# Monitor-Protection_48V.net
KiCad netlist of a schematic drawn in Altium Designer
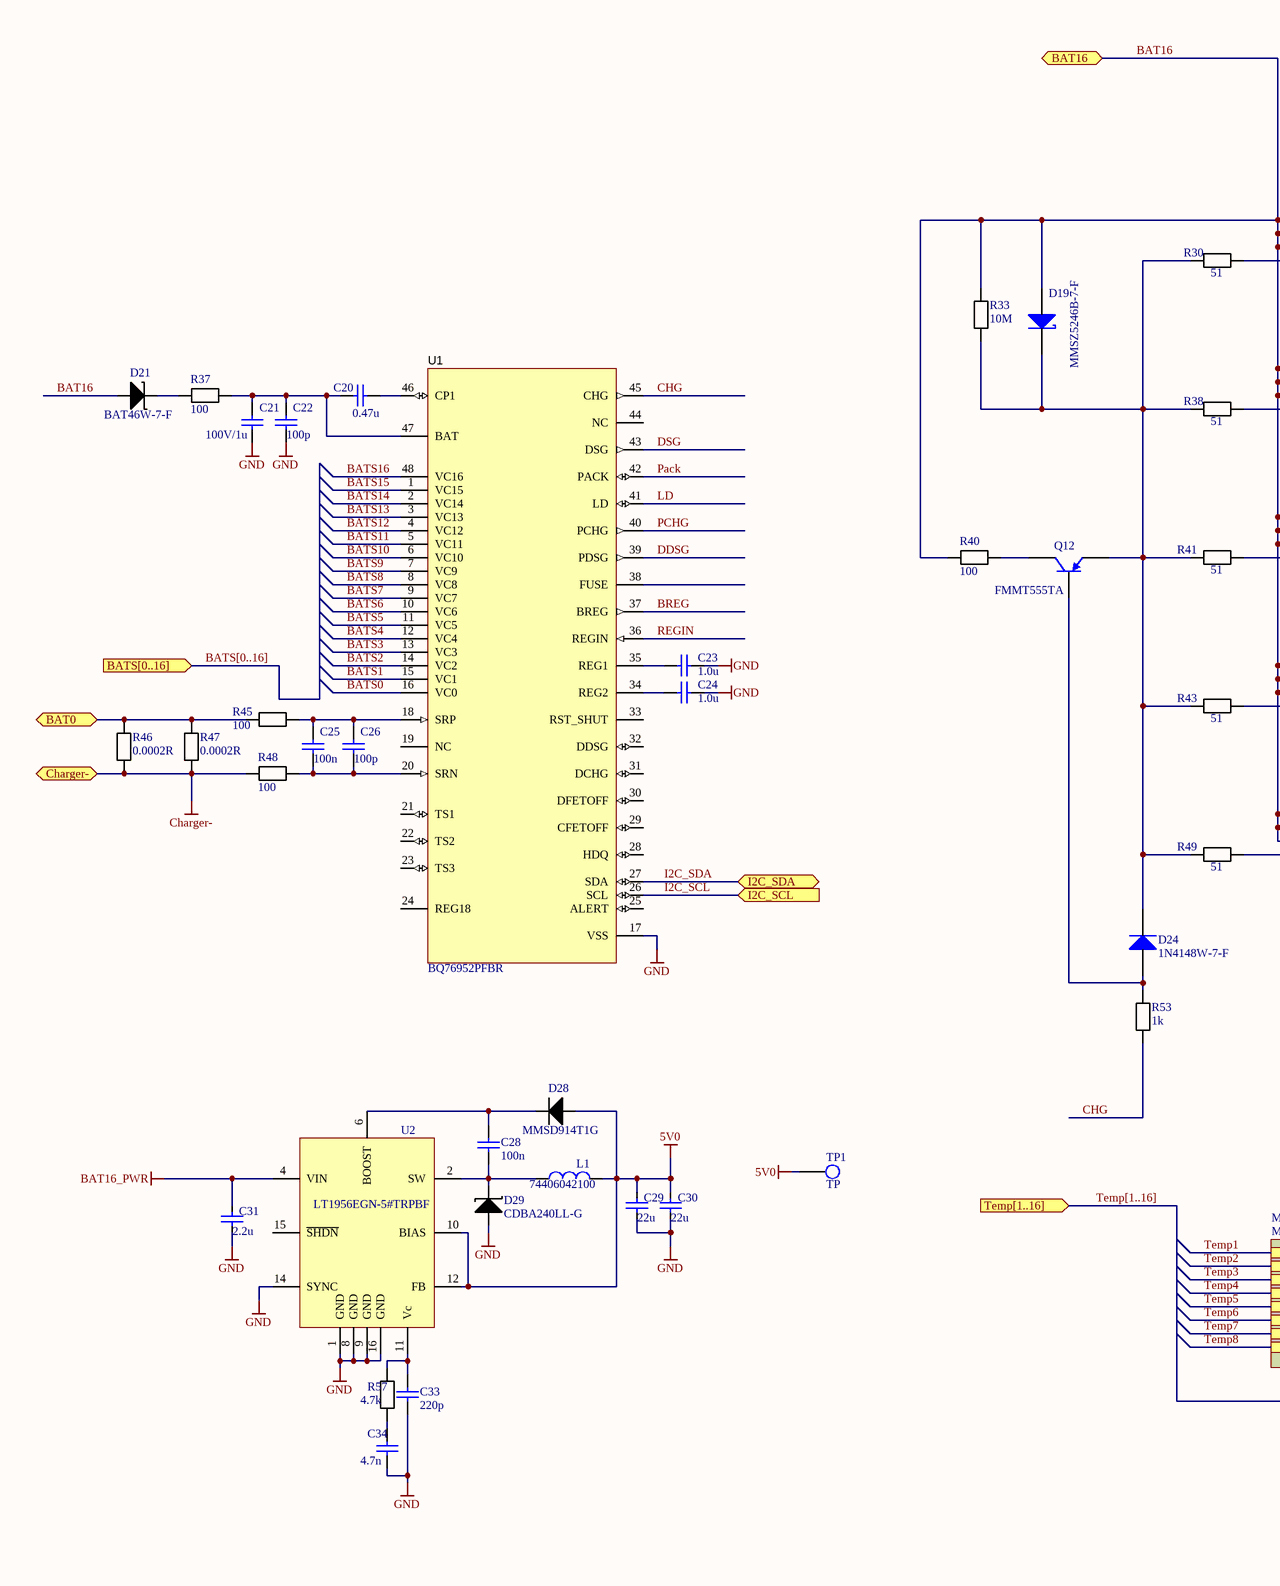
[diagram p0: Monitor-Protection_48V.SchDoc, left]
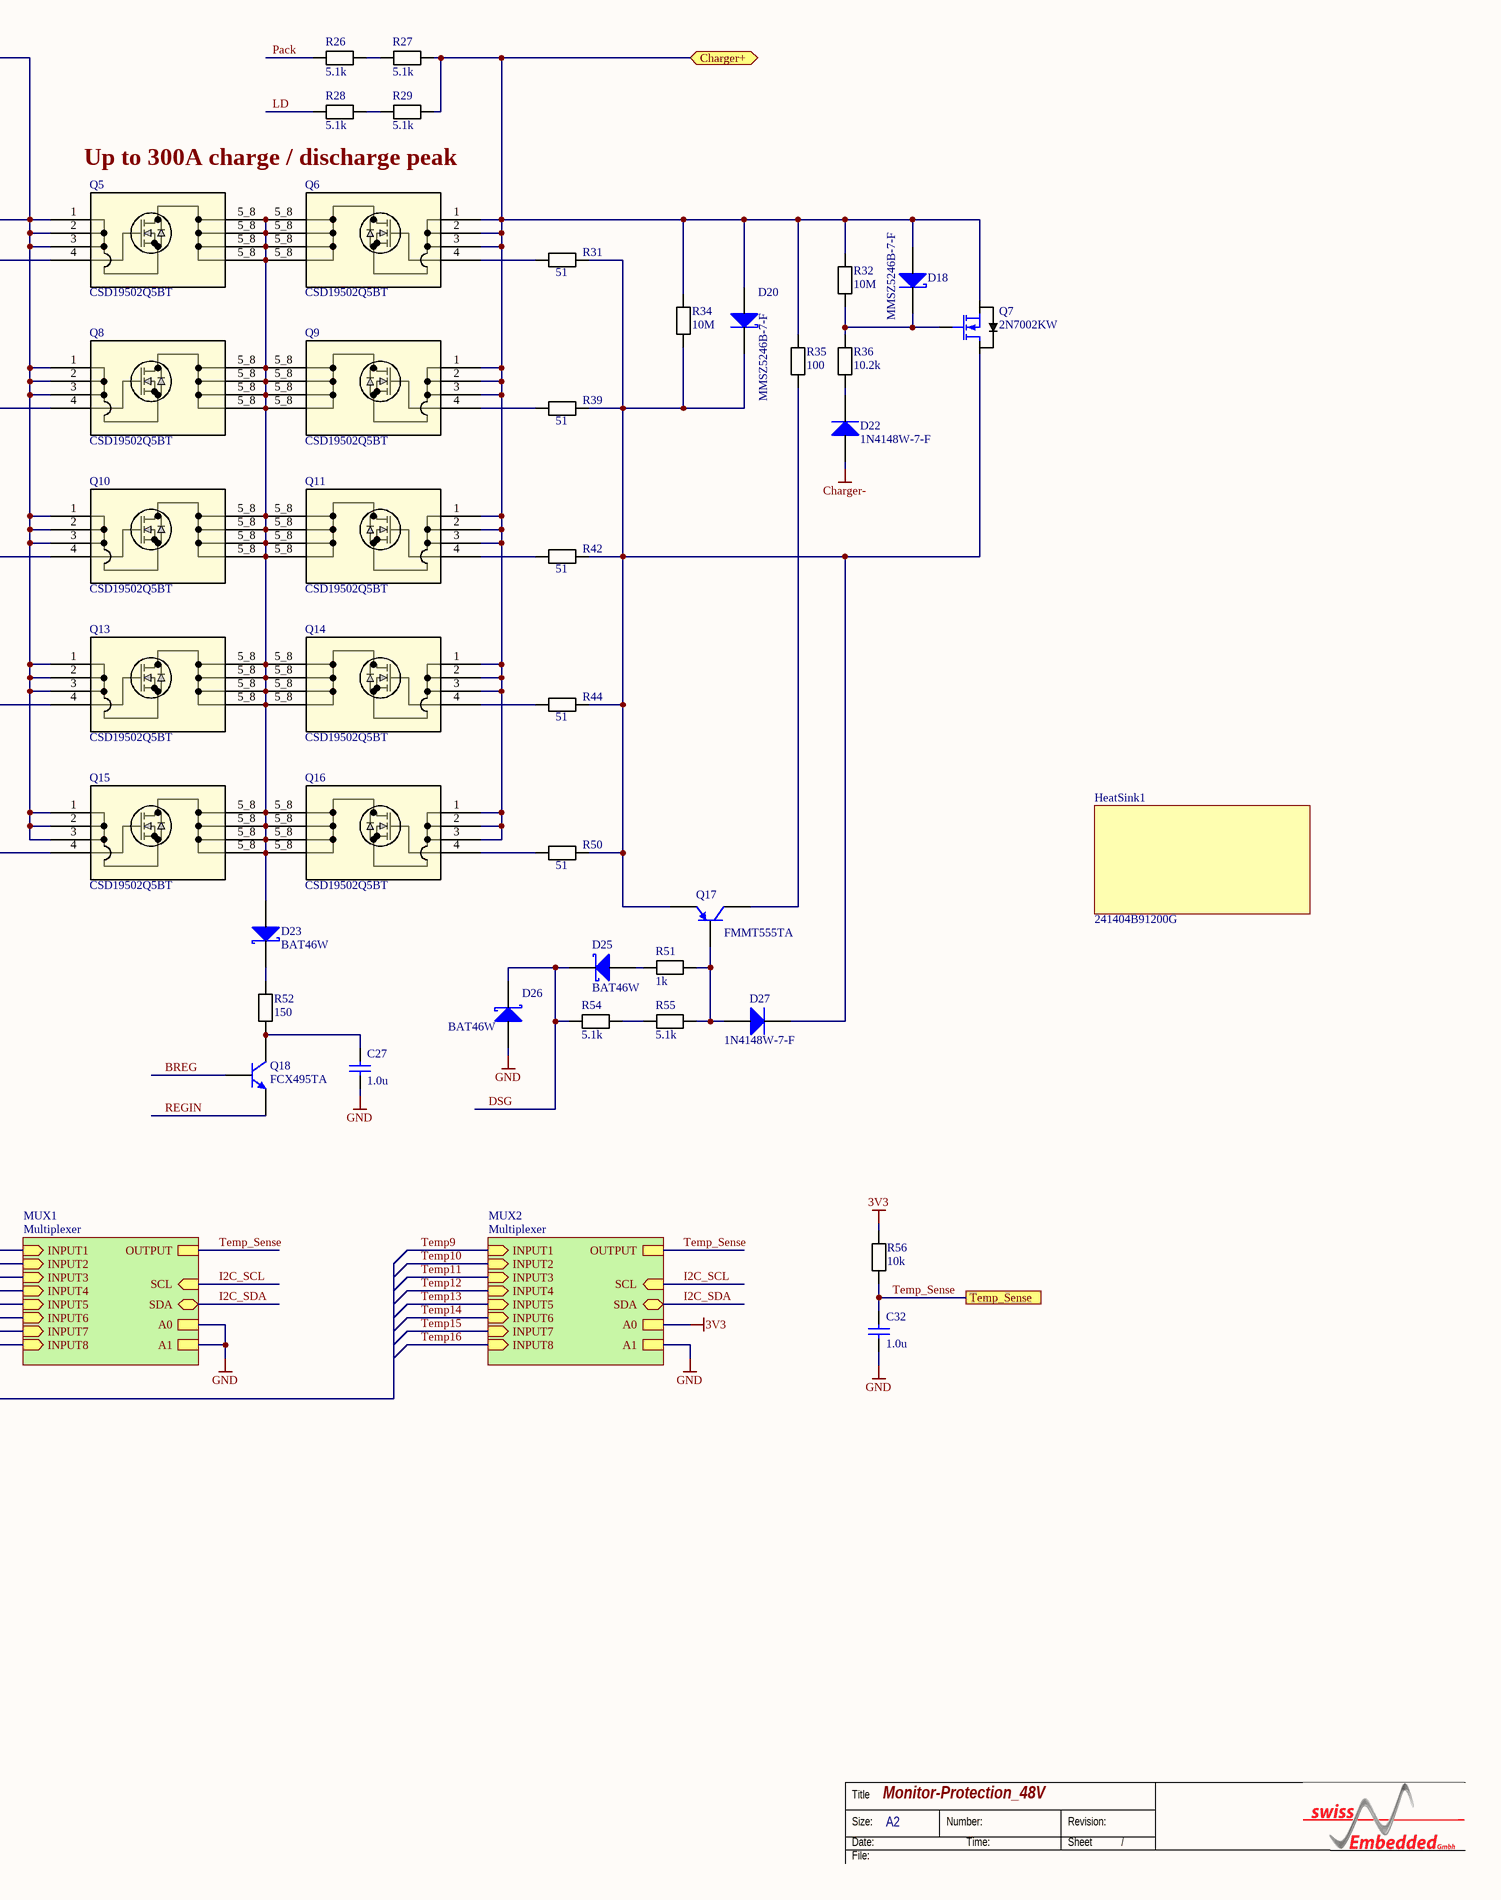
[diagram p1: Monitor-Protection_48V.SchDoc, right]

(export (version "E")
  (design (tool "Eeschema 10.0.6"))
  (components
    (comp (ref "C20")
      (value "0.47u")
      (footprint "C0805")
      (description "CAP CER 0.47UF 25V X7R 0805")
      (fields
        (field (name "MANUFACTURER") "Yageo")
        (field (name "MANUFACTURER PART NUMBER") "CC0805KKX7R8BB474")
      )
      (libsource (lib "RCL") (part "CAP"))
    )
    (comp (ref "C21")
      (value "100V/1u")
      (footprint "C1206")
      (description "Capacitor 1u 1206 +-10% 100V")
      (fields
        (field (name "MANUFACTURER") "Yageo")
        (field (name "MANUFACTURER PART NUMBER") "CC1206KKX7R0BB105")
      )
      (libsource (lib "EMDO301_Balancer_48V") (part "CC1206KKX7R0BB105"))
    )
    (comp (ref "C22")
      (value "100p")
      (footprint "C0603")
      (description "CAP CER 100PF 100V C0G/NP0 0603")
      (fields
        (field (name "MANUFACTURER") "Murata Electronics")
        (field (name "MANUFACTURER PART NUMBER") "GCM1885C2A101FA16D")
      )
      (libsource (lib "RCL") (part "CAP"))
    )
    (comp (ref "C23")
      (value "1.0u")
      (footprint "C0603")
      (description "CAP CER 1UF 25V X5R 0603")
      (fields
        (field (name "MANUFACTURER") "Yageo")
        (field (name "MANUFACTURER PART NUMBER") "CC0603KRX5R8BB105")
      )
      (libsource (lib "RCL") (part "CAP"))
    )
    (comp (ref "C24")
      (value "1.0u")
      (footprint "C0603")
      (description "CAP CER 1UF 25V X5R 0603")
      (fields
        (field (name "MANUFACTURER") "Yageo")
        (field (name "MANUFACTURER PART NUMBER") "CC0603KRX5R8BB105")
      )
      (libsource (lib "RCL") (part "CAP"))
    )
    (comp (ref "C25")
      (value "100n")
      (footprint "C0603")
      (description "Capacitor 100n 0603 +-10% 50V")
      (fields
        (field (name "PART NUMBER") "CAP_YAG_CC0603KRX7R9BB104_X7R")
        (field (name "MANUFACTURER PART NUMBER") "CC0603KRX7R9BB104")
      )
      (libsource (lib "EMDO301_Balancer_48V") (part "CAP_YAG_CC0603KRX7R9BB104_X7R"))
    )
    (comp (ref "C26")
      (value "100p")
      (footprint "C0603")
      (description "CAP CER 100PF 100V C0G/NP0 0603")
      (fields
        (field (name "MANUFACTURER") "Murata Electronics")
        (field (name "MANUFACTURER PART NUMBER") "GCM1885C2A101FA16D")
      )
      (libsource (lib "RCL") (part "CAP"))
    )
    (comp (ref "C27")
      (value "1.0u")
      (footprint "C0603")
      (description "CAP CER 1UF 25V X5R 0603")
      (fields
        (field (name "MANUFACTURER") "Yageo")
        (field (name "MANUFACTURER PART NUMBER") "CC0603KRX5R8BB105")
      )
      (libsource (lib "RCL") (part "CAP"))
    )
    (comp (ref "C28")
      (value "100n")
      (footprint "C0603")
      (description "Capacitor 100n 0603 +-10% 50V")
      (fields
        (field (name "PART NUMBER") "CAP_YAG_CC0603KRX7R9BB104_X7R")
        (field (name "MANUFACTURER PART NUMBER") "CC0603KRX7R9BB104")
      )
      (libsource (lib "EMDO301_Balancer_48V") (part "CAP_YAG_CC0603KRX7R9BB104_X7R"))
    )
    (comp (ref "C29")
      (value "22u")
      (footprint "C1210")
      (description "22µF ±10% 10V")
      (fields
        (field (name "MANUFACTURER") "Murata")
        (field (name "MANUFACTURER PART NUMBER") "GRM32ER71A226KE20L")
      )
      (libsource (lib "Miscellaneous Devices") (part "Cap"))
    )
    (comp (ref "C30")
      (value "22u")
      (footprint "C1210")
      (description "22µF ±10% 10V")
      (fields
        (field (name "MANUFACTURER") "Murata")
        (field (name "MANUFACTURER PART NUMBER") "GRM32ER71A226KE20L")
      )
      (libsource (lib "Miscellaneous Devices") (part "Cap"))
    )
    (comp (ref "C31")
      (value "2.2u")
      (footprint "C1210")
      (description "2.2µF ±10% 100V")
      (fields
        (field (name "MANUFACTURER") "Murata")
        (field (name "MANUFACTURER PART NUMBER") "GRM32ER72A225KA35K")
      )
      (libsource (lib "Miscellaneous Devices") (part "Cap"))
    )
    (comp (ref "C32")
      (value "1.0u")
      (footprint "C0603")
      (description "CAP CER 1UF 25V X5R 0603")
      (fields
        (field (name "MANUFACTURER") "Yageo")
        (field (name "MANUFACTURER PART NUMBER") "CC0603KRX5R8BB105")
      )
      (libsource (lib "RCL") (part "CAP"))
    )
    (comp (ref "C33")
      (value "220p")
      (footprint "C0603")
      (description "Capacitor 220p 0603 +-10% 50V")
      (fields
        (field (name "PART NUMBER") "CAP_YAG_CC0603KRNPO9BN221_NPO")
        (field (name "MANUFACTURER") "Yageo")
      )
      (libsource (lib "Cap_Yag_0603_NPO_50_10%$") (part "CAP_YAG_CC0603KRNPO9BN221_NPO"))
    )
    (comp (ref "C34")
      (value "4.7n")
      (footprint "C0603")
      (description "Capacitor 4.7n 0603 +-10% 50V")
      (fields
        (field (name "PART NUMBER") "CAP_YAG_CC0603KRX7R9BB472_X7R")
        (field (name "MANUFACTURER") "Yageo")
      )
      (libsource (lib "Cap_Yag_0603_X7R_50_10%$") (part "CAP_YAG_CC0603KRX7R9BB472_X7R"))
    )
    (comp (ref "D18")
      (value "MMSZ5246B-7-F")
      (footprint "SOD-323")
      (description "Diode, Zener, 16 V, 500 mW, SOD-323")
      (fields (field (name "MANUFACTURER") "Diodes") (field (name "TOLERANCE") "+-5%"))
      (libsource (lib "Battery") (part "VD_SMD_MMSZ5246B-7-F"))
    )
    (comp (ref "D19")
      (value "MMSZ5246B-7-F")
      (footprint "SOD-323")
      (description "Diode, Zener, 16 V, 500 mW, SOD-323")
      (fields (field (name "MANUFACTURER") "Diodes") (field (name "TOLERANCE") "+-5%"))
      (libsource (lib "Battery") (part "VD_SMD_MMSZ5246B-7-F"))
    )
    (comp (ref "D20")
      (value "MMSZ5246B-7-F")
      (footprint "SOD-323")
      (description "Diode, Zener, 16 V, 500 mW, SOD-323")
      (fields (field (name "MANUFACTURER") "Diodes") (field (name "TOLERANCE") "+-5%"))
      (libsource (lib "Battery") (part "VD_SMD_MMSZ5246B-7-F"))
    )
    (comp (ref "D21")
      (value "BAT46W-7-F")
      (footprint "SOD123")
      (description "DIODE SCHOTTKY 100V 150MA SOD123")
      (fields (field (name "MANUFACTURER") "Diodes Incorporated"))
      (libsource (lib "EnergyMeter") (part "BAT46W-7-F"))
    )
    (comp (ref "D22")
      (value "1N4148W-7-F")
      (footprint "SOD123")
      (description "Diode, Ultrafast, 100 V, 0.15 A, SOD-123")
      (fields (field (name "MANUFACTURER") "Diodes Inc.") (field (name "MANUFACTURER PART NUMBER") "1N4148"))
      (libsource (lib "Battery") (part "VD_SMD_1N4148"))
    )
    (comp (ref "D23")
      (value "BAT46W")
      (footprint "SOD123")
      (description "Diode, Schottky, 100 V, 0.15 A, SOD-123")
      (fields
        (field (name "MANUFACTURER") "CENTRAL SEMI")
        (field (name "MANUFACTURER PART NUMBER") "CMMSH2-40 TR")
      )
      (libsource (lib "Battery") (part "VD_SMD_BAT46W"))
    )
    (comp (ref "D24")
      (value "1N4148W-7-F")
      (footprint "SOD123")
      (description "Diode, Ultrafast, 100 V, 0.15 A, SOD-123")
      (fields (field (name "MANUFACTURER") "Diodes Inc.") (field (name "MANUFACTURER PART NUMBER") "1N4148"))
      (libsource (lib "Battery") (part "VD_SMD_1N4148"))
    )
    (comp (ref "D25")
      (value "BAT46W")
      (footprint "SOD123")
      (description "Diode, Schottky, 100 V, 0.15 A, SOD-123")
      (fields
        (field (name "MANUFACTURER") "CENTRAL SEMI")
        (field (name "MANUFACTURER PART NUMBER") "CMMSH2-40 TR")
      )
      (libsource (lib "Battery") (part "VD_SMD_BAT46W"))
    )
    (comp (ref "D26")
      (value "BAT46W")
      (footprint "SOD123")
      (description "Diode, Schottky, 100 V, 0.15 A, SOD-123")
      (fields
        (field (name "MANUFACTURER") "CENTRAL SEMI")
        (field (name "MANUFACTURER PART NUMBER") "CMMSH2-40 TR")
      )
      (libsource (lib "Battery") (part "VD_SMD_BAT46W"))
    )
    (comp (ref "D27")
      (value "1N4148W-7-F")
      (footprint "SOD123")
      (description "Diode, Ultrafast, 100 V, 0.15 A, SOD-123")
      (fields (field (name "MANUFACTURER") "Diodes Inc.") (field (name "MANUFACTURER PART NUMBER") "1N4148"))
      (libsource (lib "Battery") (part "VD_SMD_1N4148"))
    )
    (comp (ref "D28")
      (value "MMSD914T1G")
      (footprint "SOD123")
      (description "DIODE GEN PURP 100V 200MA SOD123")
      (fields (field (name "MANUFACTURER") "ON Semiconductor"))
      (libsource (lib "EnergyMeter") (part "MMSD914T1G"))
    )
    (comp (ref "D29")
      (value "CDBA240LL-G")
      (footprint "DO-214AC")
      (description "DIODE SCHOTTKY 40V 2A DO214AC")
      (fields (field (name "MANUFACTURER") "Comchip Technology"))
      (libsource (lib "EnergyMeter") (part "CDBA240LL-G"))
    )
    (comp (ref "HeatSink1")
      (value "241404B91200G")
      (footprint "HeatSink_241404B91200G")
      (description "Heat Sinks Heat Sink for Quarter Brick DC/DC Converters, Lengthwise Fins, 11.4mm Height")
      (fields (field (name "MANUFACTURER") "Aavid"))
      (libsource (lib "EMDO301_Balancer_48V") (part "HeatSink"))
    )
    (comp (ref "L1")
      (value "74406042100")
      (footprint "WURTH_74406042100")
      (description "FIXED IND 10UH 1.61A 133MOHM SMD")
      (fields (field (name "MANUFACTURER") "Würth Elektronik"))
      (libsource (lib "WirelessCharger") (part "Inductor"))
    )
    (comp (ref "Q5")
      (value "CSD19502Q5BT")
      (footprint "TRANS_CSD19502Q5BT")
      (description "MOSFET N-Channel, 3.4mOhm 80V")
      (fields (field (name "MANUFACTURER") "TI") (field (name "TOLERANCE") "+-5%"))
      (libsource (lib "Battery") (part "VT_FET_CSD19532Q5B"))
    )
    (comp (ref "Q6")
      (value "CSD19502Q5BT")
      (footprint "TRANS_CSD19502Q5BT")
      (description "MOSFET N-Channel, 3.4mOhm 80V")
      (fields (field (name "MANUFACTURER") "TI") (field (name "TOLERANCE") "+-5%"))
      (libsource (lib "Battery") (part "VT_FET_CSD19532Q5B"))
    )
    (comp (ref "Q7")
      (value "2N7002KW")
      (footprint "SOT-323")
      (description "MOSFET, N-CH, 60 V, 0.31 A, SOT-323")
      (fields (field (name "MANUFACTURER") "Fairchild"))
      (libsource (lib "Battery") (part "VT_FET_2N7002KW"))
    )
    (comp (ref "Q8")
      (value "CSD19502Q5BT")
      (footprint "TRANS_CSD19502Q5BT")
      (description "MOSFET N-Channel, 3.4mOhm 80V")
      (fields (field (name "MANUFACTURER") "TI") (field (name "TOLERANCE") "+-5%"))
      (libsource (lib "Battery") (part "VT_FET_CSD19532Q5B"))
    )
    (comp (ref "Q9")
      (value "CSD19502Q5BT")
      (footprint "TRANS_CSD19502Q5BT")
      (description "MOSFET N-Channel, 3.4mOhm 80V")
      (fields (field (name "MANUFACTURER") "TI") (field (name "TOLERANCE") "+-5%"))
      (libsource (lib "Battery") (part "VT_FET_CSD19532Q5B"))
    )
    (comp (ref "Q10")
      (value "CSD19502Q5BT")
      (footprint "TRANS_CSD19502Q5BT")
      (description "MOSFET N-Channel, 3.4mOhm 80V")
      (fields (field (name "MANUFACTURER") "TI") (field (name "TOLERANCE") "+-5%"))
      (libsource (lib "Battery") (part "VT_FET_CSD19532Q5B"))
    )
    (comp (ref "Q11")
      (value "CSD19502Q5BT")
      (footprint "TRANS_CSD19502Q5BT")
      (description "MOSFET N-Channel, 3.4mOhm 80V")
      (fields (field (name "MANUFACTURER") "TI") (field (name "TOLERANCE") "+-5%"))
      (libsource (lib "Battery") (part "VT_FET_CSD19532Q5B"))
    )
    (comp (ref "Q12")
      (value "FMMT555TA")
      (footprint "SOT23-3N")
      (description "TRANS PNP 150V 1A SOT23-3")
      (fields (field (name "MANUFACTURER") "Diodes"))
      (libsource (lib "EnergyMeter") (part "FMMT555TA"))
    )
    (comp (ref "Q13")
      (value "CSD19502Q5BT")
      (footprint "TRANS_CSD19502Q5BT")
      (description "MOSFET N-Channel, 3.4mOhm 80V")
      (fields (field (name "MANUFACTURER") "TI") (field (name "TOLERANCE") "+-5%"))
      (libsource (lib "Battery") (part "VT_FET_CSD19532Q5B"))
    )
    (comp (ref "Q14")
      (value "CSD19502Q5BT")
      (footprint "TRANS_CSD19502Q5BT")
      (description "MOSFET N-Channel, 3.4mOhm 80V")
      (fields (field (name "MANUFACTURER") "TI") (field (name "TOLERANCE") "+-5%"))
      (libsource (lib "Battery") (part "VT_FET_CSD19532Q5B"))
    )
    (comp (ref "Q15")
      (value "CSD19502Q5BT")
      (footprint "TRANS_CSD19502Q5BT")
      (description "MOSFET N-Channel, 3.4mOhm 80V")
      (fields (field (name "MANUFACTURER") "TI") (field (name "TOLERANCE") "+-5%"))
      (libsource (lib "Battery") (part "VT_FET_CSD19532Q5B"))
    )
    (comp (ref "Q16")
      (value "CSD19502Q5BT")
      (footprint "TRANS_CSD19502Q5BT")
      (description "MOSFET N-Channel, 3.4mOhm 80V")
      (fields (field (name "MANUFACTURER") "TI") (field (name "TOLERANCE") "+-5%"))
      (libsource (lib "Battery") (part "VT_FET_CSD19532Q5B"))
    )
    (comp (ref "Q17")
      (value "FMMT555TA")
      (footprint "SOT23-3N")
      (description "TRANS PNP 150V 1A SOT23-3")
      (fields (field (name "MANUFACTURER") "Diodes"))
      (libsource (lib "EnergyMeter") (part "FMMT555TA"))
    )
    (comp (ref "Q18")
      (value "FCX495TA")
      (footprint "SOT-89")
      (description "Transistor, NPN, 150 V, 1 A, AEC-Q101, SOT-89")
      (fields (field (name "MANUFACTURER") "Diodes"))
      (libsource (lib "Battery") (part "FCX495TA"))
    )
    (comp (ref "R26")
      (value "5.1k")
      (footprint "R0603")
      (description "Resistor 5.1k 0603 +-1% 0.1")
      (fields (field (name "PART NUMBER") "RES_YAG_RC0603FR-075K1L") (field (name "MANUFACTURER") "Yageo"))
      (libsource (lib "Res_Yag_0603_1%$") (part "RES_YAG_RC0603FR-075K1L"))
    )
    (comp (ref "R27")
      (value "5.1k")
      (footprint "R0603")
      (description "Resistor 5.1k 0603 +-1% 0.1")
      (fields (field (name "PART NUMBER") "RES_YAG_RC0603FR-075K1L") (field (name "MANUFACTURER") "Yageo"))
      (libsource (lib "Res_Yag_0603_1%$") (part "RES_YAG_RC0603FR-075K1L"))
    )
    (comp (ref "R28")
      (value "5.1k")
      (footprint "R0603")
      (description "Resistor 5.1k 0603 +-1% 0.1")
      (fields (field (name "PART NUMBER") "RES_YAG_RC0603FR-075K1L") (field (name "MANUFACTURER") "Yageo"))
      (libsource (lib "Res_Yag_0603_1%$") (part "RES_YAG_RC0603FR-075K1L"))
    )
    (comp (ref "R29")
      (value "5.1k")
      (footprint "R0603")
      (description "Resistor 5.1k 0603 +-1% 0.1")
      (fields (field (name "PART NUMBER") "RES_YAG_RC0603FR-075K1L") (field (name "MANUFACTURER") "Yageo"))
      (libsource (lib "Res_Yag_0603_1%$") (part "RES_YAG_RC0603FR-075K1L"))
    )
    (comp (ref "R30")
      (value "51")
      (footprint "R0603")
      (description "Resistor 51 0603 +-1% 0.1")
      (fields (field (name "PART NUMBER") "RES_YAG_RC0603FR-0751RL") (field (name "MANUFACTURER") "Yageo"))
      (libsource (lib "Res_Yag_0603_1%$") (part "RES_YAG_RC0603FR-0751RL"))
    )
    (comp (ref "R31")
      (value "51")
      (footprint "R0603")
      (description "Resistor 51 0603 +-1% 0.1")
      (fields (field (name "PART NUMBER") "RES_YAG_RC0603FR-0751RL") (field (name "MANUFACTURER") "Yageo"))
      (libsource (lib "Res_Yag_0603_1%$") (part "RES_YAG_RC0603FR-0751RL"))
    )
    (comp (ref "R32")
      (value "10M")
      (footprint "R0603")
      (description "Resistor 10M 0603 +-1% 0.1")
      (fields (field (name "PART NUMBER") "RES_YAG_RC0603FR-0710ML") (field (name "MANUFACTURER") "Yageo"))
      (libsource (lib "Res_Yag_0603_1%$") (part "RES_YAG_RC0603FR-0710ML"))
    )
    (comp (ref "R33")
      (value "10M")
      (footprint "R0603")
      (description "Resistor 10M 0603 +-1% 0.1")
      (fields (field (name "PART NUMBER") "RES_YAG_RC0603FR-0710ML") (field (name "MANUFACTURER") "Yageo"))
      (libsource (lib "Res_Yag_0603_1%$") (part "RES_YAG_RC0603FR-0710ML"))
    )
    (comp (ref "R34")
      (value "10M")
      (footprint "R0603")
      (description "Resistor 10M 0603 +-1% 0.1")
      (fields (field (name "PART NUMBER") "RES_YAG_RC0603FR-0710ML") (field (name "MANUFACTURER") "Yageo"))
      (libsource (lib "Res_Yag_0603_1%$") (part "RES_YAG_RC0603FR-0710ML"))
    )
    (comp (ref "R35")
      (value "100")
      (footprint "R0603")
      (description "Resistor 100 0603 +-1% 0.1")
      (fields (field (name "PART NUMBER") "RES_YAG_RC0603FR-07100RL") (field (name "MANUFACTURER") "Yageo"))
      (libsource (lib "Res_Yag_0603_1%$") (part "RES_YAG_RC0603FR-07100RL"))
    )
    (comp (ref "R36")
      (value "10.2k")
      (footprint "R0603")
      (description "Resistor 10.2k 0603 +-1% 0.1")
      (fields (field (name "PART NUMBER") "RES_YAG_RC0603FR-0710K2L") (field (name "MANUFACTURER") "Yageo"))
      (libsource (lib "Res_Yag_0603_1%$") (part "RES_YAG_RC0603FR-0710K2L"))
    )
    (comp (ref "R37")
      (value "100")
      (footprint "R0603")
      (description "Resistor 100 0603 +-1% 0.1")
      (fields (field (name "PART NUMBER") "RES_YAG_RC0603FR-07100RL") (field (name "MANUFACTURER") "Yageo"))
      (libsource (lib "Res_Yag_0603_1%$") (part "RES_YAG_RC0603FR-07100RL"))
    )
    (comp (ref "R38")
      (value "51")
      (footprint "R0603")
      (description "Resistor 51 0603 +-1% 0.1")
      (fields (field (name "PART NUMBER") "RES_YAG_RC0603FR-0751RL") (field (name "MANUFACTURER") "Yageo"))
      (libsource (lib "Res_Yag_0603_1%$") (part "RES_YAG_RC0603FR-0751RL"))
    )
    (comp (ref "R39")
      (value "51")
      (footprint "R0603")
      (description "Resistor 51 0603 +-1% 0.1")
      (fields (field (name "PART NUMBER") "RES_YAG_RC0603FR-0751RL") (field (name "MANUFACTURER") "Yageo"))
      (libsource (lib "Res_Yag_0603_1%$") (part "RES_YAG_RC0603FR-0751RL"))
    )
    (comp (ref "R40")
      (value "100")
      (footprint "R0603")
      (description "Resistor 100 0603 +-1% 0.1")
      (fields (field (name "PART NUMBER") "RES_YAG_RC0603FR-07100RL") (field (name "MANUFACTURER") "Yageo"))
      (libsource (lib "Res_Yag_0603_1%$") (part "RES_YAG_RC0603FR-07100RL"))
    )
    (comp (ref "R41")
      (value "51")
      (footprint "R0603")
      (description "Resistor 51 0603 +-1% 0.1")
      (fields (field (name "PART NUMBER") "RES_YAG_RC0603FR-0751RL") (field (name "MANUFACTURER") "Yageo"))
      (libsource (lib "Res_Yag_0603_1%$") (part "RES_YAG_RC0603FR-0751RL"))
    )
    (comp (ref "R42")
      (value "51")
      (footprint "R0603")
      (description "Resistor 51 0603 +-1% 0.1")
      (fields (field (name "PART NUMBER") "RES_YAG_RC0603FR-0751RL") (field (name "MANUFACTURER") "Yageo"))
      (libsource (lib "Res_Yag_0603_1%$") (part "RES_YAG_RC0603FR-0751RL"))
    )
    (comp (ref "R43")
      (value "51")
      (footprint "R0603")
      (description "Resistor 51 0603 +-1% 0.1")
      (fields (field (name "PART NUMBER") "RES_YAG_RC0603FR-0751RL") (field (name "MANUFACTURER") "Yageo"))
      (libsource (lib "Res_Yag_0603_1%$") (part "RES_YAG_RC0603FR-0751RL"))
    )
    (comp (ref "R44")
      (value "51")
      (footprint "R0603")
      (description "Resistor 51 0603 +-1% 0.1")
      (fields (field (name "PART NUMBER") "RES_YAG_RC0603FR-0751RL") (field (name "MANUFACTURER") "Yageo"))
      (libsource (lib "Res_Yag_0603_1%$") (part "RES_YAG_RC0603FR-0751RL"))
    )
    (comp (ref "R45")
      (value "100")
      (footprint "R0603")
      (description "Resistor 100 0603 +-1% 0.1")
      (fields (field (name "PART NUMBER") "RES_YAG_RC0603FR-07100RL") (field (name "MANUFACTURER") "Yageo"))
      (libsource (lib "Res_Yag_0603_1%$") (part "RES_YAG_RC0603FR-07100RL"))
    )
    (comp (ref "R46")
      (value "0.0002R")
      (footprint "RES 3920")
      (description "RES 0.0002 OHM 1% 12W 3920")
      (fields
        (field (name "MANUFACTURER") "Bourns Inc.")
        (field (name "MANUFACTURER PART NUMBER") "CSS2H-3920R-L200FE")
      )
      (libsource (lib "RCL") (part "RES"))
    )
    (comp (ref "R47")
      (value "0.0002R")
      (footprint "RES 3920")
      (description "RES 0.0002 OHM 1% 12W 3920")
      (fields
        (field (name "MANUFACTURER") "Bourns Inc.")
        (field (name "MANUFACTURER PART NUMBER") "CSS2H-3920R-L200FE")
      )
      (libsource (lib "RCL") (part "RES"))
    )
    (comp (ref "R48")
      (value "100")
      (footprint "R0603")
      (description "Resistor 100 0603 +-1% 0.1")
      (fields (field (name "PART NUMBER") "RES_YAG_RC0603FR-07100RL") (field (name "MANUFACTURER") "Yageo"))
      (libsource (lib "Res_Yag_0603_1%$") (part "RES_YAG_RC0603FR-07100RL"))
    )
    (comp (ref "R49")
      (value "51")
      (footprint "R0603")
      (description "Resistor 51 0603 +-1% 0.1")
      (fields (field (name "PART NUMBER") "RES_YAG_RC0603FR-0751RL") (field (name "MANUFACTURER") "Yageo"))
      (libsource (lib "Res_Yag_0603_1%$") (part "RES_YAG_RC0603FR-0751RL"))
    )
    (comp (ref "R50")
      (value "51")
      (footprint "R0603")
      (description "Resistor 51 0603 +-1% 0.1")
      (fields (field (name "PART NUMBER") "RES_YAG_RC0603FR-0751RL") (field (name "MANUFACTURER") "Yageo"))
      (libsource (lib "Res_Yag_0603_1%$") (part "RES_YAG_RC0603FR-0751RL"))
    )
    (comp (ref "R51")
      (value "1k")
      (footprint "R0603")
      (description "Resistor 1k 0603 +-1% 0.1")
      (fields (field (name "PART NUMBER") "RES_YAG_RC0603FR-071KL") (field (name "MANUFACTURER") "Yageo"))
      (libsource (lib "Res_Yag_0603_1%$") (part "RES_YAG_RC0603FR-071KL"))
    )
    (comp (ref "R52")
      (value "150")
      (footprint "R0603")
      (description "Resistor 150 0603 +-1% 0.1")
      (fields (field (name "PART NUMBER") "RES_YAG_RC0603FR-07150RL") (field (name "MANUFACTURER") "Yageo"))
      (libsource (lib "Res_Yag_0603_1%$") (part "RES_YAG_RC0603FR-07150RL"))
    )
    (comp (ref "R53")
      (value "1k")
      (footprint "R0603")
      (description "Resistor 1k 0603 +-1% 0.1")
      (fields (field (name "PART NUMBER") "RES_YAG_RC0603FR-071KL") (field (name "MANUFACTURER") "Yageo"))
      (libsource (lib "Res_Yag_0603_1%$") (part "RES_YAG_RC0603FR-071KL"))
    )
    (comp (ref "R54")
      (value "5.1k")
      (footprint "R0603")
      (description "Resistor 5.1k 0603 +-1% 0.1")
      (fields (field (name "PART NUMBER") "RES_YAG_RC0603FR-075K1L") (field (name "MANUFACTURER") "Yageo"))
      (libsource (lib "Res_Yag_0603_1%$") (part "RES_YAG_RC0603FR-075K1L"))
    )
    (comp (ref "R55")
      (value "5.1k")
      (footprint "R0603")
      (description "Resistor 5.1k 0603 +-1% 0.1")
      (fields (field (name "PART NUMBER") "RES_YAG_RC0603FR-075K1L") (field (name "MANUFACTURER") "Yageo"))
      (libsource (lib "Res_Yag_0603_1%$") (part "RES_YAG_RC0603FR-075K1L"))
    )
    (comp (ref "R56")
      (value "10k")
      (footprint "R0603")
      (description "Resistor 10k 0603 +-1% 0.1")
      (fields (field (name "PART NUMBER") "RES_YAG_RC0603FR-0710KL") (field (name "MANUFACTURER") "Yageo"))
      (libsource (lib "Res_Yag_0603_1%$") (part "RES_YAG_RC0603FR-0710KL"))
    )
    (comp (ref "R57")
      (value "4.7k")
      (footprint "R0603")
      (description "Resistor 4.7k 0603 +-1% 0.1")
      (fields (field (name "PART NUMBER") "RES_YAG_RC0603FR-074K7L") (field (name "MANUFACTURER") "Yageo"))
      (libsource (lib "Res_Yag_0603_1%$") (part "RES_YAG_RC0603FR-074K7L"))
    )
    (comp (ref "TP1")
      (value "TP")
      (footprint "TP")
      (description "Testpoint")
      (fields
        (field (name "MANUFACTURER") "None")
        (field (name "MANUFACTURER PART NUMBER") "Testpads, do not populate")
      )
      (libsource (lib "EnergyMeter") (part "TP"))
    )
    (comp (ref "U1")
      (value "BQ76952PFBR")
      (footprint "QFP50P900X900X120-48N")
      (description "Multicell Battery Monitor and Protection Family, Texas Instrument BQ76952PFBR")
      (fields (field (name "MANUFACTURER") "Texas Instruments"))
      (libsource (lib "EMDO301_Balancer_48V") (part "BQ76952PFBR"))
    )
    (comp (ref "U2")
      (value "LT1956EGN-5#TRPBF")
      (footprint "SSOP-16_GN")
      (description "IC REG BUCK 5V 1.5A 16SSOP")
      (fields (field (name "MANUFACTURER") "Analog Devices Inc."))
      (libsource (lib "EnergyMeter") (part "LT1956EGN-5#TRPBF"))
    )
  )
  (nets
    (net (code "1") (name "/BAT0") (class "Default")
      (node (ref "R45") (pin "1") (pinfunction "1_1") (pintype "passive"))
      (node (ref "R46") (pin "2") (pinfunction "2_2") (pintype "passive"))
      (node (ref "R47") (pin "2") (pinfunction "2_2") (pintype "passive"))
    )
    (net (code "2") (name "/BAT16") (class "Default")
      (node (ref "D19") (pin "A") (pinfunction "ANODE_A") (pintype "passive"))
      (node (ref "D21") (pin "A") (pinfunction "A_A") (pintype "passive"))
      (node (ref "Q10") (pin "1") (pinfunction "S_1") (pintype "passive"))
      (node (ref "Q10") (pin "2") (pinfunction "S_2") (pintype "passive"))
      (node (ref "Q10") (pin "3") (pinfunction "S_3") (pintype "passive"))
      (node (ref "Q13") (pin "1") (pinfunction "S_1") (pintype "passive"))
      (node (ref "Q13") (pin "2") (pinfunction "S_2") (pintype "passive"))
      (node (ref "Q13") (pin "3") (pinfunction "S_3") (pintype "passive"))
      (node (ref "Q15") (pin "1") (pinfunction "S_1") (pintype "passive"))
      (node (ref "Q15") (pin "2") (pinfunction "S_2") (pintype "passive"))
      (node (ref "Q15") (pin "3") (pinfunction "S_3") (pintype "passive"))
      (node (ref "Q5") (pin "1") (pinfunction "S_1") (pintype "passive"))
      (node (ref "Q5") (pin "2") (pinfunction "S_2") (pintype "passive"))
      (node (ref "Q5") (pin "3") (pinfunction "S_3") (pintype "passive"))
      (node (ref "Q8") (pin "1") (pinfunction "S_1") (pintype "passive"))
      (node (ref "Q8") (pin "2") (pinfunction "S_2") (pintype "passive"))
      (node (ref "Q8") (pin "3") (pinfunction "S_3") (pintype "passive"))
      (node (ref "R33") (pin "2") (pinfunction "2_2") (pintype "passive"))
      (node (ref "R40") (pin "1") (pinfunction "1_1") (pintype "passive"))
    )
    (net (code "3") (name "/BATS0") (class "Default")
      (node (ref "U1") (pin "16") (pinfunction "VC0_16") (pintype "passive"))
    )
    (net (code "4") (name "/BATS1") (class "Default")
      (node (ref "U1") (pin "15") (pinfunction "VC1_15") (pintype "passive"))
    )
    (net (code "5") (name "/BATS2") (class "Default")
      (node (ref "U1") (pin "14") (pinfunction "VC2_14") (pintype "passive"))
    )
    (net (code "6") (name "/BATS3") (class "Default")
      (node (ref "U1") (pin "13") (pinfunction "VC3_13") (pintype "passive"))
    )
    (net (code "7") (name "/BATS4") (class "Default")
      (node (ref "U1") (pin "12") (pinfunction "VC4_12") (pintype "passive"))
    )
    (net (code "8") (name "/BATS5") (class "Default")
      (node (ref "U1") (pin "11") (pinfunction "VC5_11") (pintype "passive"))
    )
    (net (code "9") (name "/BATS6") (class "Default")
      (node (ref "U1") (pin "10") (pinfunction "VC6_10") (pintype "passive"))
    )
    (net (code "10") (name "/BATS7") (class "Default")
      (node (ref "U1") (pin "9") (pinfunction "VC7_9") (pintype "passive"))
    )
    (net (code "11") (name "/BATS8") (class "Default")
      (node (ref "U1") (pin "8") (pinfunction "VC8_8") (pintype "passive"))
    )
    (net (code "12") (name "/BATS9") (class "Default")
      (node (ref "U1") (pin "7") (pinfunction "VC9_7") (pintype "passive"))
    )
    (net (code "13") (name "/BATS10") (class "Default")
      (node (ref "U1") (pin "6") (pinfunction "VC10_6") (pintype "passive"))
    )
    (net (code "14") (name "/BATS11") (class "Default")
      (node (ref "U1") (pin "5") (pinfunction "VC11_5") (pintype "passive"))
    )
    (net (code "15") (name "/BATS12") (class "Default")
      (node (ref "U1") (pin "4") (pinfunction "VC12_4") (pintype "passive"))
    )
    (net (code "16") (name "/BATS13") (class "Default")
      (node (ref "U1") (pin "3") (pinfunction "VC13_3") (pintype "passive"))
    )
    (net (code "17") (name "/BATS14") (class "Default")
      (node (ref "U1") (pin "2") (pinfunction "VC14_2") (pintype "passive"))
    )
    (net (code "18") (name "/BATS15") (class "Default")
      (node (ref "U1") (pin "1") (pinfunction "VC15_1") (pintype "passive"))
    )
    (net (code "19") (name "/BATS16") (class "Default")
      (node (ref "U1") (pin "48") (pinfunction "VC16_48") (pintype "passive"))
    )
    (net (code "21") (name "/BREG") (class "Default")
      (node (ref "Q18") (pin "1") (pinfunction "B_1") (pintype "passive"))
      (node (ref "U1") (pin "37") (pinfunction "BREG_37") (pintype "output"))
    )
    (net (code "22") (name "/CHG") (class "Default")
      (node (ref "R53") (pin "1") (pinfunction "1_1") (pintype "passive"))
      (node (ref "U1") (pin "45") (pinfunction "CHG_45") (pintype "output"))
    )
    (net (code "23") (name "/Charger+") (class "Default")
      (node (ref "D18") (pin "A") (pinfunction "ANODE_A") (pintype "passive"))
      (node (ref "D20") (pin "A") (pinfunction "ANODE_A") (pintype "passive"))
      (node (ref "Q11") (pin "1") (pinfunction "S_1") (pintype "passive"))
      (node (ref "Q11") (pin "2") (pinfunction "S_2") (pintype "passive"))
      (node (ref "Q11") (pin "3") (pinfunction "S_3") (pintype "passive"))
      (node (ref "Q14") (pin "1") (pinfunction "S_1") (pintype "passive"))
      (node (ref "Q14") (pin "2") (pinfunction "S_2") (pintype "passive"))
      (node (ref "Q14") (pin "3") (pinfunction "S_3") (pintype "passive"))
      (node (ref "Q16") (pin "1") (pinfunction "S_1") (pintype "passive"))
      (node (ref "Q16") (pin "2") (pinfunction "S_2") (pintype "passive"))
      (node (ref "Q16") (pin "3") (pinfunction "S_3") (pintype "passive"))
      (node (ref "Q6") (pin "1") (pinfunction "S_1") (pintype "passive"))
      (node (ref "Q6") (pin "2") (pinfunction "S_2") (pintype "passive"))
      (node (ref "Q6") (pin "3") (pinfunction "S_3") (pintype "passive"))
      (node (ref "Q7") (pin "2") (pinfunction "S_2") (pintype "passive"))
      (node (ref "Q9") (pin "1") (pinfunction "S_1") (pintype "passive"))
      (node (ref "Q9") (pin "2") (pinfunction "S_2") (pintype "passive"))
      (node (ref "Q9") (pin "3") (pinfunction "S_3") (pintype "passive"))
      (node (ref "R27") (pin "1") (pinfunction "1_1") (pintype "passive"))
      (node (ref "R29") (pin "1") (pinfunction "1_1") (pintype "passive"))
      (node (ref "R32") (pin "2") (pinfunction "2_2") (pintype "passive"))
      (node (ref "R34") (pin "2") (pinfunction "2_2") (pintype "passive"))
      (node (ref "R35") (pin "2") (pinfunction "2_2") (pintype "passive"))
    )
    (net (code "24") (name "/DDSG") (class "Default")
      (node (ref "U1") (pin "39") (pinfunction "PDSG_39") (pintype "output"))
    )
    (net (code "25") (name "/DSG") (class "Default")
      (node (ref "D25") (pin "C") (pinfunction "CATHODE_C") (pintype "passive"))
      (node (ref "D26") (pin "C") (pinfunction "CATHODE_C") (pintype "passive"))
      (node (ref "R54") (pin "1") (pinfunction "1_1") (pintype "passive"))
      (node (ref "U1") (pin "43") (pinfunction "DSG_43") (pintype "output"))
    )
    (net (code "26") (name "/I2C_SCL") (class "Default")
      (node (ref "U1") (pin "26") (pinfunction "SCL_26") (pintype "bidirectional"))
    )
    (net (code "27") (name "/I2C_SDA") (class "Default")
      (node (ref "U1") (pin "27") (pinfunction "SDA_27") (pintype "bidirectional"))
    )
    (net (code "28") (name "/LD") (class "Default")
      (node (ref "R28") (pin "2") (pinfunction "2_2") (pintype "passive"))
      (node (ref "U1") (pin "41") (pinfunction "LD_41") (pintype "bidirectional"))
    )
    (net (code "29") (name "/PCHG") (class "Default")
      (node (ref "U1") (pin "40") (pinfunction "PCHG_40") (pintype "output"))
    )
    (net (code "30") (name "/Pack") (class "Default")
      (node (ref "R26") (pin "2") (pinfunction "2_2") (pintype "passive"))
      (node (ref "U1") (pin "42") (pinfunction "PACK_42") (pintype "bidirectional"))
    )
    (net (code "31") (name "/REGIN") (class "Default")
      (node (ref "Q18") (pin "3") (pinfunction "E_3") (pintype "passive"))
      (node (ref "U1") (pin "36") (pinfunction "REGIN_36") (pintype "input"))
    )
    (net (code "49") (name "/Temp_Sense") (class "Default")
      (node (ref "C32") (pin "1") (pinfunction "1_1") (pintype "passive"))
      (node (ref "R56") (pin "1") (pinfunction "1_1") (pintype "passive"))
    )
    (net (code "50") (name "3V3") (class "Default")
      (node (ref "R56") (pin "2") (pinfunction "2_2") (pintype "passive"))
    )
    (net (code "51") (name "5V0") (class "Default")
      (node (ref "C29") (pin "1") (pinfunction "1_1") (pintype "passive"))
      (node (ref "C30") (pin "1") (pinfunction "1_1") (pintype "passive"))
      (node (ref "D28") (pin "A") (pinfunction "A_A") (pintype "passive"))
      (node (ref "L1") (pin "2") (pinfunction "2_2") (pintype "passive"))
      (node (ref "TP1") (pin "1") (pinfunction "TCT_1") (pintype "passive"))
      (node (ref "U2") (pin "10") (pinfunction "BIAS_10") (pintype "passive"))
      (node (ref "U2") (pin "12") (pinfunction "FB_12") (pintype "passive"))
    )
    (net (code "52") (name "BAT16_PWR") (class "Default")
      (node (ref "C31") (pin "1") (pinfunction "1_1") (pintype "passive"))
      (node (ref "U2") (pin "4") (pinfunction "VIN_4") (pintype "passive"))
    )
    (net (code "53") (name "Charger-") (class "Default")
      (node (ref "D22") (pin "A") (pinfunction "ANODE_A") (pintype "passive"))
      (node (ref "R46") (pin "1") (pinfunction "1_1") (pintype "passive"))
      (node (ref "R47") (pin "1") (pinfunction "1_1") (pintype "passive"))
      (node (ref "R48") (pin "1") (pinfunction "1_1") (pintype "passive"))
    )
    (net (code "54") (name "GND") (class "Default")
      (node (ref "C21") (pin "1") (pinfunction "1_1") (pintype "passive"))
      (node (ref "C22") (pin "1") (pinfunction "1_1") (pintype "passive"))
      (node (ref "C23") (pin "1") (pinfunction "1_1") (pintype "passive"))
      (node (ref "C24") (pin "1") (pinfunction "1_1") (pintype "passive"))
      (node (ref "C27") (pin "2") (pinfunction "2_2") (pintype "passive"))
      (node (ref "C29") (pin "2") (pinfunction "2_2") (pintype "passive"))
      (node (ref "C30") (pin "2") (pinfunction "2_2") (pintype "passive"))
      (node (ref "C31") (pin "2") (pinfunction "2_2") (pintype "passive"))
      (node (ref "C32") (pin "2") (pinfunction "2_2") (pintype "passive"))
      (node (ref "C33") (pin "1") (pinfunction "1_1") (pintype "passive"))
      (node (ref "C34") (pin "1") (pinfunction "1_1") (pintype "passive"))
      (node (ref "D26") (pin "A") (pinfunction "ANODE_A") (pintype "passive"))
      (node (ref "D29") (pin "A") (pinfunction "A_A") (pintype "passive"))
      (node (ref "U1") (pin "17") (pinfunction "VSS_17") (pintype "power_in"))
      (node (ref "U2") (pin "1") (pinfunction "GND_1") (pintype "passive"))
      (node (ref "U2") (pin "14") (pinfunction "SYNC_14") (pintype "passive"))
      (node (ref "U2") (pin "16") (pinfunction "GND_16") (pintype "passive"))
      (node (ref "U2") (pin "8") (pinfunction "GND_8") (pintype "passive"))
      (node (ref "U2") (pin "9") (pinfunction "GND_9") (pintype "passive"))
    )
    (net (code "55") (name "Net-(C34-Pad2)") (class "Default")
      (node (ref "C34") (pin "2") (pinfunction "2_2") (pintype "passive"))
      (node (ref "R57") (pin "1") (pinfunction "1_1") (pintype "passive"))
    )
    (net (code "56") (name "Net-(D18-CATHODE)") (class "Default")
      (node (ref "D18") (pin "C") (pinfunction "CATHODE_C") (pintype "passive"))
      (node (ref "Q7") (pin "1") (pinfunction "G_1") (pintype "passive"))
      (node (ref "R32") (pin "1") (pinfunction "1_1") (pintype "passive"))
      (node (ref "R36") (pin "2") (pinfunction "2_2") (pintype "passive"))
    )
    (net (code "57") (name "Net-(D19-CATHODE)") (class "Default")
      (node (ref "D19") (pin "C") (pinfunction "CATHODE_C") (pintype "passive"))
      (node (ref "D24") (pin "C") (pinfunction "CATHODE_C") (pintype "passive"))
      (node (ref "Q12") (pin "2") (pinfunction "E_2") (pintype "passive"))
      (node (ref "R30") (pin "1") (pinfunction "1_1") (pintype "passive"))
      (node (ref "R33") (pin "1") (pinfunction "1_1") (pintype "passive"))
      (node (ref "R38") (pin "1") (pinfunction "1_1") (pintype "passive"))
      (node (ref "R41") (pin "1") (pinfunction "1_1") (pintype "passive"))
      (node (ref "R43") (pin "1") (pinfunction "1_1") (pintype "passive"))
      (node (ref "R49") (pin "1") (pinfunction "1_1") (pintype "passive"))
    )
    (net (code "58") (name "Net-(D20-CATHODE)") (class "Default")
      (node (ref "D20") (pin "C") (pinfunction "CATHODE_C") (pintype "passive"))
      (node (ref "D27") (pin "C") (pinfunction "CATHODE_C") (pintype "passive"))
      (node (ref "Q17") (pin "2") (pinfunction "E_2") (pintype "passive"))
      (node (ref "Q7") (pin "3") (pinfunction "D_3") (pintype "passive"))
      (node (ref "R31") (pin "2") (pinfunction "2_2") (pintype "passive"))
      (node (ref "R34") (pin "1") (pinfunction "1_1") (pintype "passive"))
      (node (ref "R39") (pin "2") (pinfunction "2_2") (pintype "passive"))
      (node (ref "R42") (pin "2") (pinfunction "2_2") (pintype "passive"))
      (node (ref "R44") (pin "2") (pinfunction "2_2") (pintype "passive"))
      (node (ref "R50") (pin "2") (pinfunction "2_2") (pintype "passive"))
    )
    (net (code "59") (name "Net-(D21-PadC)") (class "Default")
      (node (ref "D21") (pin "C") (pinfunction "C_C") (pintype "passive"))
      (node (ref "R37") (pin "1") (pinfunction "1_1") (pintype "passive"))
    )
    (net (code "60") (name "Net-(D22-CATHODE)") (class "Default")
      (node (ref "D22") (pin "C") (pinfunction "CATHODE_C") (pintype "passive"))
      (node (ref "R36") (pin "1") (pinfunction "1_1") (pintype "passive"))
    )
    (net (code "61") (name "Net-(D23-ANODE)") (class "Default")
      (node (ref "D23") (pin "A") (pinfunction "ANODE_A") (pintype "passive"))
      (node (ref "Q10") (pin "5_8") (pinfunction "D_5_8") (pintype "passive"))
      (node (ref "Q11") (pin "5_8") (pinfunction "D_5_8") (pintype "passive"))
      (node (ref "Q13") (pin "5_8") (pinfunction "D_5_8") (pintype "passive"))
      (node (ref "Q14") (pin "5_8") (pinfunction "D_5_8") (pintype "passive"))
      (node (ref "Q15") (pin "5_8") (pinfunction "D_5_8") (pintype "passive"))
      (node (ref "Q16") (pin "5_8") (pinfunction "D_5_8") (pintype "passive"))
      (node (ref "Q5") (pin "5_8") (pinfunction "D_5_8") (pintype "passive"))
      (node (ref "Q6") (pin "5_8") (pinfunction "D_5_8") (pintype "passive"))
      (node (ref "Q8") (pin "5_8") (pinfunction "D_5_8") (pintype "passive"))
      (node (ref "Q9") (pin "5_8") (pinfunction "D_5_8") (pintype "passive"))
    )
    (net (code "62") (name "Net-(D23-CATHODE)") (class "Default")
      (node (ref "D23") (pin "C") (pinfunction "CATHODE_C") (pintype "passive"))
      (node (ref "R52") (pin "2") (pinfunction "2_2") (pintype "passive"))
    )
    (net (code "63") (name "Net-(D24-ANODE)") (class "Default")
      (node (ref "D24") (pin "A") (pinfunction "ANODE_A") (pintype "passive"))
      (node (ref "Q12") (pin "1") (pinfunction "B_1") (pintype "passive"))
      (node (ref "R53") (pin "2") (pinfunction "2_2") (pintype "passive"))
    )
    (net (code "64") (name "Net-(D25-ANODE)") (class "Default")
      (node (ref "D25") (pin "A") (pinfunction "ANODE_A") (pintype "passive"))
      (node (ref "R51") (pin "2") (pinfunction "2_2") (pintype "passive"))
    )
    (net (code "65") (name "Net-(D27-ANODE)") (class "Default")
      (node (ref "D27") (pin "A") (pinfunction "ANODE_A") (pintype "passive"))
      (node (ref "Q17") (pin "1") (pinfunction "B_1") (pintype "passive"))
      (node (ref "R51") (pin "1") (pinfunction "1_1") (pintype "passive"))
      (node (ref "R55") (pin "2") (pinfunction "2_2") (pintype "passive"))
    )
    (net (code "66") (name "Net-(Q5-G)") (class "Default")
      (node (ref "Q5") (pin "4") (pinfunction "G_4") (pintype "passive"))
      (node (ref "R30") (pin "2") (pinfunction "2_2") (pintype "passive"))
    )
    (net (code "67") (name "Net-(Q6-G)") (class "Default")
      (node (ref "Q6") (pin "4") (pinfunction "G_4") (pintype "passive"))
      (node (ref "R31") (pin "1") (pinfunction "1_1") (pintype "passive"))
    )
    (net (code "68") (name "Net-(Q8-G)") (class "Default")
      (node (ref "Q8") (pin "4") (pinfunction "G_4") (pintype "passive"))
      (node (ref "R38") (pin "2") (pinfunction "2_2") (pintype "passive"))
    )
    (net (code "69") (name "Net-(Q9-G)") (class "Default")
      (node (ref "Q9") (pin "4") (pinfunction "G_4") (pintype "passive"))
      (node (ref "R39") (pin "1") (pinfunction "1_1") (pintype "passive"))
    )
    (net (code "70") (name "Net-(Q10-G)") (class "Default")
      (node (ref "Q10") (pin "4") (pinfunction "G_4") (pintype "passive"))
      (node (ref "R41") (pin "2") (pinfunction "2_2") (pintype "passive"))
    )
    (net (code "71") (name "Net-(Q11-G)") (class "Default")
      (node (ref "Q11") (pin "4") (pinfunction "G_4") (pintype "passive"))
      (node (ref "R42") (pin "1") (pinfunction "1_1") (pintype "passive"))
    )
    (net (code "72") (name "Net-(Q12-C)") (class "Default")
      (node (ref "Q12") (pin "3") (pinfunction "C_3") (pintype "passive"))
      (node (ref "R40") (pin "2") (pinfunction "2_2") (pintype "passive"))
    )
    (net (code "73") (name "Net-(Q13-G)") (class "Default")
      (node (ref "Q13") (pin "4") (pinfunction "G_4") (pintype "passive"))
      (node (ref "R43") (pin "2") (pinfunction "2_2") (pintype "passive"))
    )
    (net (code "74") (name "Net-(Q14-G)") (class "Default")
      (node (ref "Q14") (pin "4") (pinfunction "G_4") (pintype "passive"))
      (node (ref "R44") (pin "1") (pinfunction "1_1") (pintype "passive"))
    )
    (net (code "75") (name "Net-(Q15-G)") (class "Default")
      (node (ref "Q15") (pin "4") (pinfunction "G_4") (pintype "passive"))
      (node (ref "R49") (pin "2") (pinfunction "2_2") (pintype "passive"))
    )
    (net (code "76") (name "Net-(Q16-G)") (class "Default")
      (node (ref "Q16") (pin "4") (pinfunction "G_4") (pintype "passive"))
      (node (ref "R50") (pin "1") (pinfunction "1_1") (pintype "passive"))
    )
    (net (code "77") (name "Net-(Q17-C)") (class "Default")
      (node (ref "Q17") (pin "3") (pinfunction "C_3") (pintype "passive"))
      (node (ref "R35") (pin "1") (pinfunction "1_1") (pintype "passive"))
    )
    (net (code "78") (name "Net-(Q18-C)") (class "Default")
      (node (ref "C27") (pin "1") (pinfunction "1_1") (pintype "passive"))
      (node (ref "Q18") (pin "2") (pinfunction "C_2") (pintype "passive"))
      (node (ref "R52") (pin "1") (pinfunction "1_1") (pintype "passive"))
    )
    (net (code "79") (name "Net-(R26-Pad1)") (class "Default")
      (node (ref "R26") (pin "1") (pinfunction "1_1") (pintype "passive"))
      (node (ref "R27") (pin "2") (pinfunction "2_2") (pintype "passive"))
    )
    (net (code "80") (name "Net-(R28-Pad1)") (class "Default")
      (node (ref "R28") (pin "1") (pinfunction "1_1") (pintype "passive"))
      (node (ref "R29") (pin "2") (pinfunction "2_2") (pintype "passive"))
    )
    (net (code "81") (name "Net-(R54-Pad2)") (class "Default")
      (node (ref "R54") (pin "2") (pinfunction "2_2") (pintype "passive"))
      (node (ref "R55") (pin "1") (pinfunction "1_1") (pintype "passive"))
    )
    (net (code "82") (name "Net-(U1-BAT)") (class "Default")
      (node (ref "C20") (pin "2") (pinfunction "2_2") (pintype "passive"))
      (node (ref "C21") (pin "2") (pinfunction "2_2") (pintype "passive"))
      (node (ref "C22") (pin "2") (pinfunction "2_2") (pintype "passive"))
      (node (ref "R37") (pin "2") (pinfunction "2_2") (pintype "passive"))
      (node (ref "U1") (pin "47") (pinfunction "BAT_47") (pintype "power_in"))
    )
    (net (code "83") (name "Net-(U1-CP1)") (class "Default")
      (node (ref "C20") (pin "1") (pinfunction "1_1") (pintype "passive"))
      (node (ref "U1") (pin "46") (pinfunction "CP1_46") (pintype "bidirectional"))
    )
    (net (code "84") (name "Net-(U1-REG1)") (class "Default")
      (node (ref "C23") (pin "2") (pinfunction "2_2") (pintype "passive"))
      (node (ref "U1") (pin "35") (pinfunction "REG1_35") (pintype "power_in"))
    )
    (net (code "85") (name "Net-(U1-REG2)") (class "Default")
      (node (ref "C24") (pin "2") (pinfunction "2_2") (pintype "passive"))
      (node (ref "U1") (pin "34") (pinfunction "REG2_34") (pintype "power_in"))
    )
    (net (code "86") (name "Net-(U1-SRN)") (class "Default")
      (node (ref "C25") (pin "1") (pinfunction "1_1") (pintype "passive"))
      (node (ref "C26") (pin "1") (pinfunction "1_1") (pintype "passive"))
      (node (ref "R48") (pin "2") (pinfunction "2_2") (pintype "passive"))
      (node (ref "U1") (pin "20") (pinfunction "SRN_20") (pintype "input"))
    )
    (net (code "87") (name "Net-(U1-SRP)") (class "Default")
      (node (ref "C25") (pin "2") (pinfunction "2_2") (pintype "passive"))
      (node (ref "C26") (pin "2") (pinfunction "2_2") (pintype "passive"))
      (node (ref "R45") (pin "2") (pinfunction "2_2") (pintype "passive"))
      (node (ref "U1") (pin "18") (pinfunction "SRP_18") (pintype "input"))
    )
    (net (code "88") (name "Net-(U2A-BOOST)") (class "Default")
      (node (ref "C28") (pin "2") (pinfunction "2_2") (pintype "passive"))
      (node (ref "D28") (pin "C") (pinfunction "C_C") (pintype "passive"))
      (node (ref "U2") (pin "6") (pinfunction "BOOST_6") (pintype "passive"))
    )
    (net (code "89") (name "Net-(U2A-SW)") (class "Default")
      (node (ref "C28") (pin "1") (pinfunction "1_1") (pintype "passive"))
      (node (ref "D29") (pin "C") (pinfunction "C_C") (pintype "passive"))
      (node (ref "L1") (pin "1") (pinfunction "1_1") (pintype "passive"))
      (node (ref "U2") (pin "2") (pinfunction "SW_2") (pintype "passive"))
    )
    (net (code "90") (name "Net-(U2A-Vc)") (class "Default")
      (node (ref "C33") (pin "2") (pinfunction "2_2") (pintype "passive"))
      (node (ref "R57") (pin "2") (pinfunction "2_2") (pintype "passive"))
      (node (ref "U2") (pin "11") (pinfunction "Vc_11") (pintype "passive"))
    )
    (net (code "91") (name "unconnected-(U1-ALERT-Pad25)") (class "Default")
      (node (ref "U1") (pin "25") (pinfunction "ALERT_25") (pintype "bidirectional"))
    )
    (net (code "92") (name "unconnected-(U1-CFETOFF-Pad29)") (class "Default")
      (node (ref "U1") (pin "29") (pinfunction "CFETOFF_29") (pintype "bidirectional"))
    )
    (net (code "93") (name "unconnected-(U1-DCHG-Pad31)") (class "Default")
      (node (ref "U1") (pin "31") (pinfunction "DCHG_31") (pintype "bidirectional"))
    )
    (net (code "94") (name "unconnected-(U1-DDSG-Pad32)") (class "Default")
      (node (ref "U1") (pin "32") (pinfunction "DDSG_32") (pintype "bidirectional"))
    )
    (net (code "95") (name "unconnected-(U1-DFETOFF-Pad30)") (class "Default")
      (node (ref "U1") (pin "30") (pinfunction "DFETOFF_30") (pintype "bidirectional"))
    )
    (net (code "96") (name "unconnected-(U1-FUSE-Pad38)") (class "Default")
      (node (ref "U1") (pin "38") (pinfunction "FUSE_38") (pintype "passive"))
    )
    (net (code "97") (name "unconnected-(U1-HDQ-Pad28)") (class "Default")
      (node (ref "U1") (pin "28") (pinfunction "HDQ_28") (pintype "bidirectional"))
    )
    (net (code "98") (name "unconnected-(U1-NC-Pad19)") (class "Default")
      (node (ref "U1") (pin "19") (pinfunction "NC_19") (pintype "passive"))
    )
    (net (code "99") (name "unconnected-(U1-NC-Pad44)") (class "Default")
      (node (ref "U1") (pin "44") (pinfunction "NC_44") (pintype "passive"))
    )
    (net (code "100") (name "unconnected-(U1-REG18-Pad24)") (class "Default")
      (node (ref "U1") (pin "24") (pinfunction "REG18_24") (pintype "power_in"))
    )
    (net (code "101") (name "unconnected-(U1-RST_SHUT-Pad33)") (class "Default")
      (node (ref "U1") (pin "33") (pinfunction "RST_SHUT_33") (pintype "passive"))
    )
    (net (code "102") (name "unconnected-(U1-TS1-Pad21)") (class "Default")
      (node (ref "U1") (pin "21") (pinfunction "TS1_21") (pintype "bidirectional"))
    )
    (net (code "103") (name "unconnected-(U1-TS2-Pad22)") (class "Default")
      (node (ref "U1") (pin "22") (pinfunction "TS2_22") (pintype "bidirectional"))
    )
    (net (code "104") (name "unconnected-(U1-TS3-Pad23)") (class "Default")
      (node (ref "U1") (pin "23") (pinfunction "TS3_23") (pintype "bidirectional"))
    )
    (net (code "105") (name "unconnected-(U2A-~{SHDN}-Pad15)") (class "Default")
      (node (ref "U2") (pin "15") (pinfunction "~{SHDN}_15") (pintype "passive"))
    )
  )
)
